# TrailerWiringSchem.net
KiCad netlist of a schematic drawn in Altium Designer
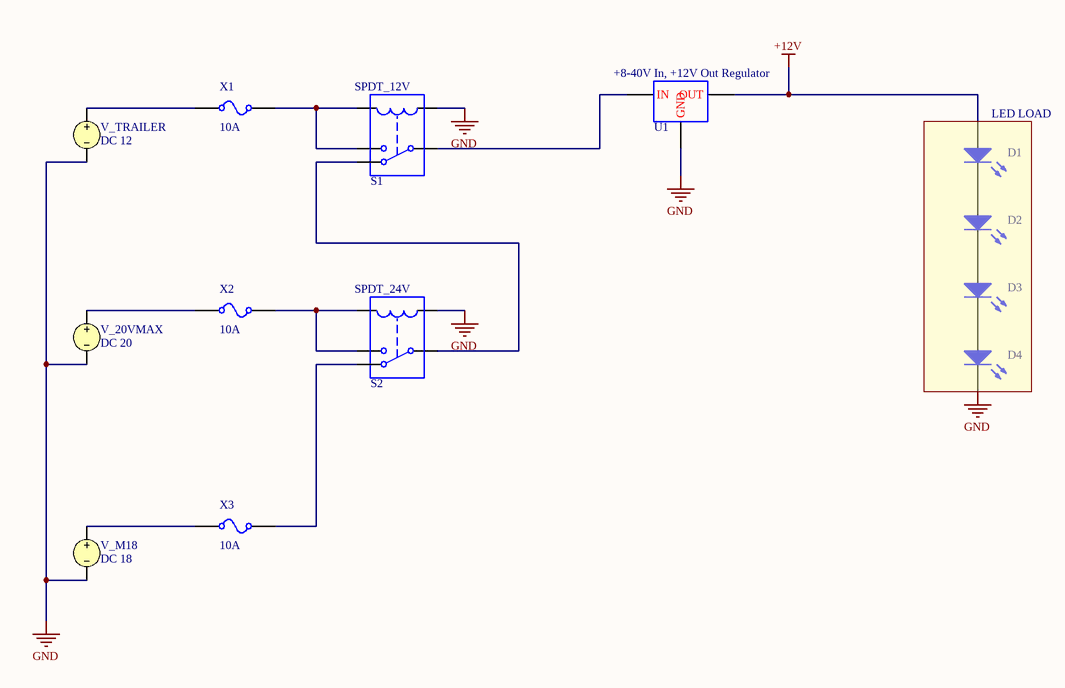
[diagram p0: TrailerWiringSchem.SchDoc]

(export (version "E")
  (design (tool "Eeschema 10.0.6"))
  (components
    (comp (ref "D1")
      (value "Light-Emitting Diode")
      (libsource (lib "Simulation Generic Components") (part "LED"))
    )
    (comp (ref "D2")
      (value "Light-Emitting Diode")
      (libsource (lib "Simulation Generic Components") (part "LED"))
    )
    (comp (ref "D3")
      (value "Light-Emitting Diode")
      (libsource (lib "Simulation Generic Components") (part "LED"))
    )
    (comp (ref "D4")
      (value "Light-Emitting Diode")
      (libsource (lib "Simulation Generic Components") (part "LED"))
    )
    (comp (ref "S1")
      (value "SPDT_12V")
      (description "Single-Pole, Double-Throw Relay")
      (libsource (lib "Simulation Generic Components") (part "SPDT Relay"))
    )
    (comp (ref "S2")
      (value "SPDT_24V")
      (description "Single-Pole, Double-Throw Relay")
      (libsource (lib "Simulation Generic Components") (part "SPDT Relay"))
    )
    (comp (ref "U1")
      (value "+8-40V In, +12V Out Regulator")
      (description "Positive Fixed Voltage regulator")
      (libsource (lib "Simulation Generic Components") (part "Linear Voltage Regulator (Fixed)"))
    )
    (comp (ref "V_20VMAX")
      (value "DC 20")
      (description "Voltage Source")
      (fields (field (name "PUBLISHER") "Altium Limited"))
      (libsource (lib "Simulation Generic Components") (part "VSRC"))
    )
    (comp (ref "V_M18")
      (value "DC 18")
      (description "Voltage Source")
      (fields (field (name "PUBLISHER") "Altium Limited"))
      (libsource (lib "Simulation Generic Components") (part "VSRC"))
    )
    (comp (ref "V_TRAILER")
      (value "DC 12")
      (description "Voltage Source")
      (fields (field (name "PUBLISHER") "Altium Limited"))
      (libsource (lib "Simulation Generic Components") (part "VSRC"))
    )
    (comp (ref "X1")
      (value "Fuse")
      (fields (field (name "CURRENT") "10A"))
      (libsource (lib "Simulation Generic Components") (part "Fuse"))
    )
    (comp (ref "X2")
      (value "Fuse")
      (fields (field (name "CURRENT") "10A"))
      (libsource (lib "Simulation Generic Components") (part "Fuse"))
    )
    (comp (ref "X3")
      (value "Fuse")
      (fields (field (name "CURRENT") "10A"))
      (libsource (lib "Simulation Generic Components") (part "Fuse"))
    )
  )
  (nets
    (net (code "1") (name "+12V") (class "Default")
      (node (ref "D1") (pin "1") (pinfunction "A_1") (pintype "passive"))
      (node (ref "U1") (pin "3") (pinfunction "OUT_3") (pintype "passive"))
    )
    (net (code "2") (name "GND") (class "Default")
      (node (ref "D4") (pin "2") (pinfunction "K_2") (pintype "passive"))
      (node (ref "S1") (pin "4") (pinfunction "4_4") (pintype "passive"))
      (node (ref "S2") (pin "4") (pinfunction "4_4") (pintype "passive"))
      (node (ref "U1") (pin "2") (pinfunction "GND_2") (pintype "passive"))
      (node (ref "V_20VMAX") (pin "2") (pinfunction "2_2") (pintype "passive"))
      (node (ref "V_M18") (pin "2") (pinfunction "2_2") (pintype "passive"))
      (node (ref "V_TRAILER") (pin "2") (pinfunction "2_2") (pintype "passive"))
    )
    (net (code "3") (name "Net-(D1-K)") (class "Default")
      (node (ref "D1") (pin "2") (pinfunction "K_2") (pintype "passive"))
      (node (ref "D2") (pin "1") (pinfunction "A_1") (pintype "passive"))
    )
    (net (code "4") (name "Net-(D2-K)") (class "Default")
      (node (ref "D2") (pin "2") (pinfunction "K_2") (pintype "passive"))
      (node (ref "D3") (pin "1") (pinfunction "A_1") (pintype "passive"))
    )
    (net (code "5") (name "Net-(D3-K)") (class "Default")
      (node (ref "D3") (pin "2") (pinfunction "K_2") (pintype "passive"))
      (node (ref "D4") (pin "1") (pinfunction "A_1") (pintype "passive"))
    )
    (net (code "6") (name "Net-(S1-Pad2)") (class "Default")
      (node (ref "S1") (pin "2") (pinfunction "2_2") (pintype "passive"))
      (node (ref "S1") (pin "5") (pinfunction "5_5") (pintype "passive"))
      (node (ref "X1") (pin "2") (pinfunction "2_2") (pintype "passive"))
    )
    (net (code "7") (name "Net-(S1-Pad3)") (class "Default")
      (node (ref "S1") (pin "3") (pinfunction "3_3") (pintype "passive"))
      (node (ref "S2") (pin "1") (pinfunction "1_1") (pintype "passive"))
    )
    (net (code "8") (name "Net-(S2-Pad2)") (class "Default")
      (node (ref "S2") (pin "2") (pinfunction "2_2") (pintype "passive"))
      (node (ref "S2") (pin "5") (pinfunction "5_5") (pintype "passive"))
      (node (ref "X2") (pin "2") (pinfunction "2_2") (pintype "passive"))
    )
    (net (code "9") (name "Net-(S2-Pad3)") (class "Default")
      (node (ref "S2") (pin "3") (pinfunction "3_3") (pintype "passive"))
      (node (ref "X3") (pin "2") (pinfunction "2_2") (pintype "passive"))
    )
    (net (code "10") (name "Net-(U1-IN)") (class "Default")
      (node (ref "S1") (pin "1") (pinfunction "1_1") (pintype "passive"))
      (node (ref "U1") (pin "1") (pinfunction "IN_1") (pintype "passive"))
    )
    (net (code "11") (name "Net-(V_20VMAX-Pad1)") (class "Default")
      (node (ref "V_20VMAX") (pin "1") (pinfunction "1_1") (pintype "passive"))
      (node (ref "X2") (pin "1") (pinfunction "1_1") (pintype "passive"))
    )
    (net (code "12") (name "Net-(V_M18-Pad1)") (class "Default")
      (node (ref "V_M18") (pin "1") (pinfunction "1_1") (pintype "passive"))
      (node (ref "X3") (pin "1") (pinfunction "1_1") (pintype "passive"))
    )
    (net (code "13") (name "Net-(V_TRAILER-Pad1)") (class "Default")
      (node (ref "V_TRAILER") (pin "1") (pinfunction "1_1") (pintype "passive"))
      (node (ref "X1") (pin "1") (pinfunction "1_1") (pintype "passive"))
    )
  )
)
